# top.net
KiCad netlist of a schematic drawn in Altium Designer
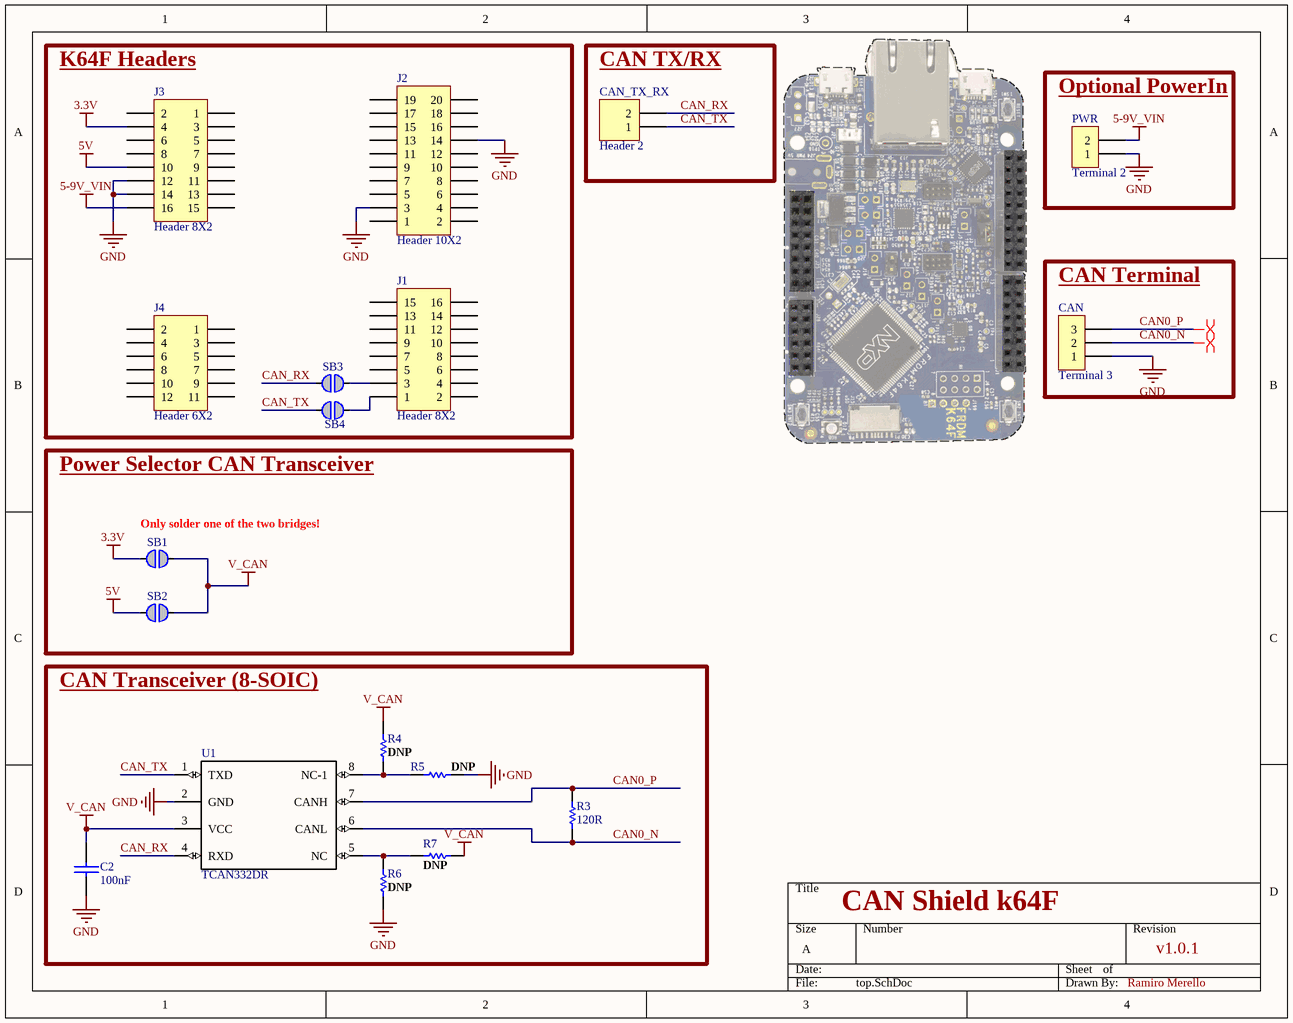
[diagram p0: top.SchDoc]

(export (version "E")
  (design (tool "Eeschema 10.0.6"))
  (components
    (comp (ref "C2")
      (value "100nF")
      (footprint "0805")
      (fields (field (name "Comment") "CDecoup"))
      (libsource (lib "FSAE ITBA") (part "CAP"))
    )
    (comp (ref "CAN")
      (value "Terminal 3")
      (footprint "BORNERA3")
      (libsource (lib "FSAE ITBA") (part "BORNERA 3"))
    )
    (comp (ref "CAN_TX_RX")
      (value "Header 2")
      (footprint "HDR1X2")
      (description "Header, 2-Pin")
      (fields (field (name "PUBLISHER") "Altium Limited"))
      (libsource (lib "Miscellaneous Connectors") (part "Header 2"))
    )
    (comp (ref "J1")
      (value "Header 8X2")
      (footprint "HDR2X8")
      (description "Header, 8-Pin, Dual row")
      (fields (field (name "PUBLISHER") "Altium Limited"))
      (libsource (lib "") (part "Header 8X2_1"))
    )
    (comp (ref "J2")
      (value "Header 10X2")
      (footprint "HDR2X10")
      (description "Header, 10-Pin, Dual row")
      (fields (field (name "PUBLISHER") "Altium Limited"))
      (libsource (lib "Miscellaneous Connectors") (part "Header 10X2"))
    )
    (comp (ref "J3")
      (value "Header 8X2")
      (footprint "HDR2X8")
      (description "Header, 8-Pin, Dual row")
      (fields (field (name "PUBLISHER") "Altium Limited"))
      (libsource (lib "Miscellaneous Connectors") (part "Header 8X2"))
    )
    (comp (ref "J4")
      (value "Header 6X2")
      (footprint "HDR2X6")
      (description "Header, 6-Pin, Dual row")
      (fields (field (name "PUBLISHER") "Altium Limited"))
      (libsource (lib "Miscellaneous Connectors") (part "Header 6X2"))
    )
    (comp (ref "PWR")
      (value "Terminal 2")
      (footprint "BORNERA2")
      (libsource (lib "FSAE ITBA") (part "BORNERA 2"))
    )
    (comp (ref "R3")
      (value "120R")
      (footprint "0805")
      (fields (field (name "Comment") "RES"))
      (libsource (lib "FSAE ITBA") (part "RES"))
    )
    (comp (ref "R4")
      (value "DNP")
      (footprint "0805")
      (description "Pullup")
      (libsource (lib "FSAE ITBA") (part "RES"))
    )
    (comp (ref "R5") (value "DNP") (footprint "0805") (libsource (lib "FSAE ITBA") (part "RES")))
    (comp (ref "R6") (value "DNP") (footprint "0805") (libsource (lib "FSAE ITBA") (part "RES")))
    (comp (ref "R7") (value "DNP") (footprint "0805") (libsource (lib "FSAE ITBA") (part "RES")))
    (comp (ref "SB1")
      (value "Solderbridge")
      (footprint "Solderbridge")
      (fields (field (name "PUBLISHER") "Nordic Semiconductor"))
      (libsource (lib "FSAE ITBA") (part "SOLDERBRIDGE"))
    )
    (comp (ref "SB2")
      (value "Solderbridge")
      (footprint "Solderbridge")
      (fields (field (name "PUBLISHER") "Nordic Semiconductor"))
      (libsource (lib "FSAE ITBA") (part "SOLDERBRIDGE"))
    )
    (comp (ref "SB3")
      (value "Solderbridge")
      (footprint "Solderbridge")
      (fields (field (name "PUBLISHER") "Nordic Semiconductor"))
      (libsource (lib "FSAE ITBA") (part "SOLDERBRIDGE"))
    )
    (comp (ref "SB4")
      (value "Solderbridge")
      (footprint "Solderbridge")
      (fields (field (name "PUBLISHER") "Nordic Semiconductor"))
      (libsource (lib "FSAE ITBA") (part "SOLDERBRIDGE"))
    )
    (comp (ref "U1")
      (value "TCAN332DR")
      (footprint "SOIC127P600X175-8N")
      (description "3.3-V CAN Transceivers with CAN FD _Flexible Data Rate_ 8-SOIC -40 to 125")
      (fields (field (name "MF") "Texas Instruments"))
      (libsource (lib "FSAE ITBA") (part "TCAN332DR"))
    )
  )
  (nets
    (net (code "1") (name "/CAN0_N") (class "Default")
      (node (ref "CAN") (pin "2") (pinfunction "2_2") (pintype "passive"))
      (node (ref "R3") (pin "1") (pinfunction "1_1") (pintype "passive"))
      (node (ref "U1") (pin "6") (pinfunction "CANL_6") (pintype "bidirectional"))
    )
    (net (code "2") (name "/CAN0_P") (class "Default")
      (node (ref "CAN") (pin "3") (pinfunction "3_3") (pintype "passive"))
      (node (ref "R3") (pin "2") (pinfunction "2_2") (pintype "passive"))
      (node (ref "U1") (pin "7") (pinfunction "CANH_7") (pintype "bidirectional"))
    )
    (net (code "3") (name "/CAN_RX") (class "Default")
      (node (ref "CAN_TX_RX") (pin "2") (pinfunction "2_2") (pintype "passive"))
      (node (ref "SB3") (pin "2") (pinfunction "1_2") (pintype "passive"))
      (node (ref "U1") (pin "4") (pinfunction "RXD_4") (pintype "bidirectional"))
    )
    (net (code "4") (name "/CAN_TX") (class "Default")
      (node (ref "CAN_TX_RX") (pin "1") (pinfunction "1_1") (pintype "passive"))
      (node (ref "SB4") (pin "2") (pinfunction "1_2") (pintype "passive"))
      (node (ref "U1") (pin "1") (pinfunction "TXD_1") (pintype "bidirectional"))
    )
    (net (code "5") (name "3.3V") (class "Default")
      (node (ref "J3") (pin "4") (pinfunction "4_4") (pintype "passive"))
      (node (ref "SB1") (pin "2") (pinfunction "1_2") (pintype "passive"))
    )
    (net (code "6") (name "5-9V_VIN") (class "Default")
      (node (ref "J3") (pin "16") (pinfunction "16_16") (pintype "passive"))
      (node (ref "PWR") (pin "2") (pinfunction "2_2") (pintype "passive"))
    )
    (net (code "7") (name "5V") (class "Default")
      (node (ref "J3") (pin "10") (pinfunction "10_10") (pintype "passive"))
      (node (ref "SB2") (pin "2") (pinfunction "1_2") (pintype "passive"))
    )
    (net (code "8") (name "GND") (class "Default")
      (node (ref "C2") (pin "2") (pinfunction "2_2") (pintype "passive"))
      (node (ref "CAN") (pin "1") (pinfunction "1_1") (pintype "passive"))
      (node (ref "J2") (pin "14") (pinfunction "14_14") (pintype "passive"))
      (node (ref "J2") (pin "3") (pinfunction "3_3") (pintype "passive"))
      (node (ref "J3") (pin "12") (pinfunction "12_12") (pintype "passive"))
      (node (ref "J3") (pin "14") (pinfunction "14_14") (pintype "passive"))
      (node (ref "PWR") (pin "1") (pinfunction "1_1") (pintype "passive"))
      (node (ref "R5") (pin "2") (pinfunction "2_2") (pintype "passive"))
      (node (ref "R6") (pin "2") (pinfunction "2_2") (pintype "passive"))
      (node (ref "U1") (pin "2") (pinfunction "GND_2") (pintype "power_in"))
    )
    (net (code "9") (name "Net-(SB3-0)") (class "Default")
      (node (ref "J1") (pin "3") (pinfunction "3_3") (pintype "passive"))
      (node (ref "SB3") (pin "1") (pinfunction "0_1") (pintype "passive"))
    )
    (net (code "10") (name "Net-(SB4-0)") (class "Default")
      (node (ref "J1") (pin "1") (pinfunction "1_1") (pintype "passive"))
      (node (ref "SB4") (pin "1") (pinfunction "0_1") (pintype "passive"))
    )
    (net (code "11") (name "Net-(U1-NC)") (class "Default")
      (node (ref "R6") (pin "1") (pinfunction "1_1") (pintype "passive"))
      (node (ref "R7") (pin "2") (pinfunction "2_2") (pintype "passive"))
      (node (ref "U1") (pin "5") (pinfunction "NC_5") (pintype "bidirectional"))
    )
    (net (code "12") (name "Net-(U1-NC-1)") (class "Default")
      (node (ref "R4") (pin "2") (pinfunction "2_2") (pintype "passive"))
      (node (ref "R5") (pin "1") (pinfunction "1_1") (pintype "passive"))
      (node (ref "U1") (pin "8") (pinfunction "NC-1_8") (pintype "bidirectional"))
    )
    (net (code "13") (name "V_CAN") (class "Default")
      (node (ref "C2") (pin "1") (pinfunction "1_1") (pintype "passive"))
      (node (ref "R4") (pin "1") (pinfunction "1_1") (pintype "passive"))
      (node (ref "R7") (pin "1") (pinfunction "1_1") (pintype "passive"))
      (node (ref "SB1") (pin "1") (pinfunction "0_1") (pintype "passive"))
      (node (ref "SB2") (pin "1") (pinfunction "0_1") (pintype "passive"))
      (node (ref "U1") (pin "3") (pinfunction "VCC_3") (pintype "power_in"))
    )
    (net (code "14") (name "unconnected-(J1-Pad2)") (class "Default")
      (node (ref "J1") (pin "2") (pinfunction "2_2") (pintype "passive"))
    )
    (net (code "15") (name "unconnected-(J1-Pad4)") (class "Default")
      (node (ref "J1") (pin "4") (pinfunction "4_4") (pintype "passive"))
    )
    (net (code "16") (name "unconnected-(J1-Pad5)") (class "Default")
      (node (ref "J1") (pin "5") (pinfunction "5_5") (pintype "passive"))
    )
    (net (code "17") (name "unconnected-(J1-Pad6)") (class "Default")
      (node (ref "J1") (pin "6") (pinfunction "6_6") (pintype "passive"))
    )
    (net (code "18") (name "unconnected-(J1-Pad7)") (class "Default")
      (node (ref "J1") (pin "7") (pinfunction "7_7") (pintype "passive"))
    )
    (net (code "19") (name "unconnected-(J1-Pad8)") (class "Default")
      (node (ref "J1") (pin "8") (pinfunction "8_8") (pintype "passive"))
    )
    (net (code "20") (name "unconnected-(J1-Pad9)") (class "Default")
      (node (ref "J1") (pin "9") (pinfunction "9_9") (pintype "passive"))
    )
    (net (code "21") (name "unconnected-(J1-Pad10)") (class "Default")
      (node (ref "J1") (pin "10") (pinfunction "10_10") (pintype "passive"))
    )
    (net (code "22") (name "unconnected-(J1-Pad11)") (class "Default")
      (node (ref "J1") (pin "11") (pinfunction "11_11") (pintype "passive"))
    )
    (net (code "23") (name "unconnected-(J1-Pad12)") (class "Default")
      (node (ref "J1") (pin "12") (pinfunction "12_12") (pintype "passive"))
    )
    (net (code "24") (name "unconnected-(J1-Pad13)") (class "Default")
      (node (ref "J1") (pin "13") (pinfunction "13_13") (pintype "passive"))
    )
    (net (code "25") (name "unconnected-(J1-Pad14)") (class "Default")
      (node (ref "J1") (pin "14") (pinfunction "14_14") (pintype "passive"))
    )
    (net (code "26") (name "unconnected-(J1-Pad15)") (class "Default")
      (node (ref "J1") (pin "15") (pinfunction "15_15") (pintype "passive"))
    )
    (net (code "27") (name "unconnected-(J1-Pad16)") (class "Default")
      (node (ref "J1") (pin "16") (pinfunction "16_16") (pintype "passive"))
    )
    (net (code "28") (name "unconnected-(J2-Pad1)") (class "Default")
      (node (ref "J2") (pin "1") (pinfunction "1_1") (pintype "passive"))
    )
    (net (code "29") (name "unconnected-(J2-Pad2)") (class "Default")
      (node (ref "J2") (pin "2") (pinfunction "2_2") (pintype "passive"))
    )
    (net (code "30") (name "unconnected-(J2-Pad4)") (class "Default")
      (node (ref "J2") (pin "4") (pinfunction "4_4") (pintype "passive"))
    )
    (net (code "31") (name "unconnected-(J2-Pad5)") (class "Default")
      (node (ref "J2") (pin "5") (pinfunction "5_5") (pintype "passive"))
    )
    (net (code "32") (name "unconnected-(J2-Pad6)") (class "Default")
      (node (ref "J2") (pin "6") (pinfunction "6_6") (pintype "passive"))
    )
    (net (code "33") (name "unconnected-(J2-Pad7)") (class "Default")
      (node (ref "J2") (pin "7") (pinfunction "7_7") (pintype "passive"))
    )
    (net (code "34") (name "unconnected-(J2-Pad8)") (class "Default")
      (node (ref "J2") (pin "8") (pinfunction "8_8") (pintype "passive"))
    )
    (net (code "35") (name "unconnected-(J2-Pad9)") (class "Default")
      (node (ref "J2") (pin "9") (pinfunction "9_9") (pintype "passive"))
    )
    (net (code "36") (name "unconnected-(J2-Pad10)") (class "Default")
      (node (ref "J2") (pin "10") (pinfunction "10_10") (pintype "passive"))
    )
    (net (code "37") (name "unconnected-(J2-Pad11)") (class "Default")
      (node (ref "J2") (pin "11") (pinfunction "11_11") (pintype "passive"))
    )
    (net (code "38") (name "unconnected-(J2-Pad12)") (class "Default")
      (node (ref "J2") (pin "12") (pinfunction "12_12") (pintype "passive"))
    )
    (net (code "39") (name "unconnected-(J2-Pad13)") (class "Default")
      (node (ref "J2") (pin "13") (pinfunction "13_13") (pintype "passive"))
    )
    (net (code "40") (name "unconnected-(J2-Pad15)") (class "Default")
      (node (ref "J2") (pin "15") (pinfunction "15_15") (pintype "passive"))
    )
    (net (code "41") (name "unconnected-(J2-Pad16)") (class "Default")
      (node (ref "J2") (pin "16") (pinfunction "16_16") (pintype "passive"))
    )
    (net (code "42") (name "unconnected-(J2-Pad17)") (class "Default")
      (node (ref "J2") (pin "17") (pinfunction "17_17") (pintype "passive"))
    )
    (net (code "43") (name "unconnected-(J2-Pad18)") (class "Default")
      (node (ref "J2") (pin "18") (pinfunction "18_18") (pintype "passive"))
    )
    (net (code "44") (name "unconnected-(J2-Pad19)") (class "Default")
      (node (ref "J2") (pin "19") (pinfunction "19_19") (pintype "passive"))
    )
    (net (code "45") (name "unconnected-(J2-Pad20)") (class "Default")
      (node (ref "J2") (pin "20") (pinfunction "20_20") (pintype "passive"))
    )
    (net (code "46") (name "unconnected-(J3-Pad1)") (class "Default")
      (node (ref "J3") (pin "1") (pinfunction "1_1") (pintype "passive"))
    )
    (net (code "47") (name "unconnected-(J3-Pad2)") (class "Default")
      (node (ref "J3") (pin "2") (pinfunction "2_2") (pintype "passive"))
    )
    (net (code "48") (name "unconnected-(J3-Pad3)") (class "Default")
      (node (ref "J3") (pin "3") (pinfunction "3_3") (pintype "passive"))
    )
    (net (code "49") (name "unconnected-(J3-Pad5)") (class "Default")
      (node (ref "J3") (pin "5") (pinfunction "5_5") (pintype "passive"))
    )
    (net (code "50") (name "unconnected-(J3-Pad6)") (class "Default")
      (node (ref "J3") (pin "6") (pinfunction "6_6") (pintype "passive"))
    )
    (net (code "51") (name "unconnected-(J3-Pad7)") (class "Default")
      (node (ref "J3") (pin "7") (pinfunction "7_7") (pintype "passive"))
    )
    (net (code "52") (name "unconnected-(J3-Pad8)") (class "Default")
      (node (ref "J3") (pin "8") (pinfunction "8_8") (pintype "passive"))
    )
    (net (code "53") (name "unconnected-(J3-Pad9)") (class "Default")
      (node (ref "J3") (pin "9") (pinfunction "9_9") (pintype "passive"))
    )
    (net (code "54") (name "unconnected-(J3-Pad11)") (class "Default")
      (node (ref "J3") (pin "11") (pinfunction "11_11") (pintype "passive"))
    )
    (net (code "55") (name "unconnected-(J3-Pad13)") (class "Default")
      (node (ref "J3") (pin "13") (pinfunction "13_13") (pintype "passive"))
    )
    (net (code "56") (name "unconnected-(J3-Pad15)") (class "Default")
      (node (ref "J3") (pin "15") (pinfunction "15_15") (pintype "passive"))
    )
    (net (code "57") (name "unconnected-(J4-Pad1)") (class "Default")
      (node (ref "J4") (pin "1") (pinfunction "1_1") (pintype "passive"))
    )
    (net (code "58") (name "unconnected-(J4-Pad2)") (class "Default")
      (node (ref "J4") (pin "2") (pinfunction "2_2") (pintype "passive"))
    )
    (net (code "59") (name "unconnected-(J4-Pad3)") (class "Default")
      (node (ref "J4") (pin "3") (pinfunction "3_3") (pintype "passive"))
    )
    (net (code "60") (name "unconnected-(J4-Pad4)") (class "Default")
      (node (ref "J4") (pin "4") (pinfunction "4_4") (pintype "passive"))
    )
    (net (code "61") (name "unconnected-(J4-Pad5)") (class "Default")
      (node (ref "J4") (pin "5") (pinfunction "5_5") (pintype "passive"))
    )
    (net (code "62") (name "unconnected-(J4-Pad6)") (class "Default")
      (node (ref "J4") (pin "6") (pinfunction "6_6") (pintype "passive"))
    )
    (net (code "63") (name "unconnected-(J4-Pad7)") (class "Default")
      (node (ref "J4") (pin "7") (pinfunction "7_7") (pintype "passive"))
    )
    (net (code "64") (name "unconnected-(J4-Pad8)") (class "Default")
      (node (ref "J4") (pin "8") (pinfunction "8_8") (pintype "passive"))
    )
    (net (code "65") (name "unconnected-(J4-Pad9)") (class "Default")
      (node (ref "J4") (pin "9") (pinfunction "9_9") (pintype "passive"))
    )
    (net (code "66") (name "unconnected-(J4-Pad10)") (class "Default")
      (node (ref "J4") (pin "10") (pinfunction "10_10") (pintype "passive"))
    )
    (net (code "67") (name "unconnected-(J4-Pad11)") (class "Default")
      (node (ref "J4") (pin "11") (pinfunction "11_11") (pintype "passive"))
    )
    (net (code "68") (name "unconnected-(J4-Pad12)") (class "Default")
      (node (ref "J4") (pin "12") (pinfunction "12_12") (pintype "passive"))
    )
  )
)
